# test-board-molex-bias-tee.net
KiCad netlist of a schematic drawn in Altium Designer
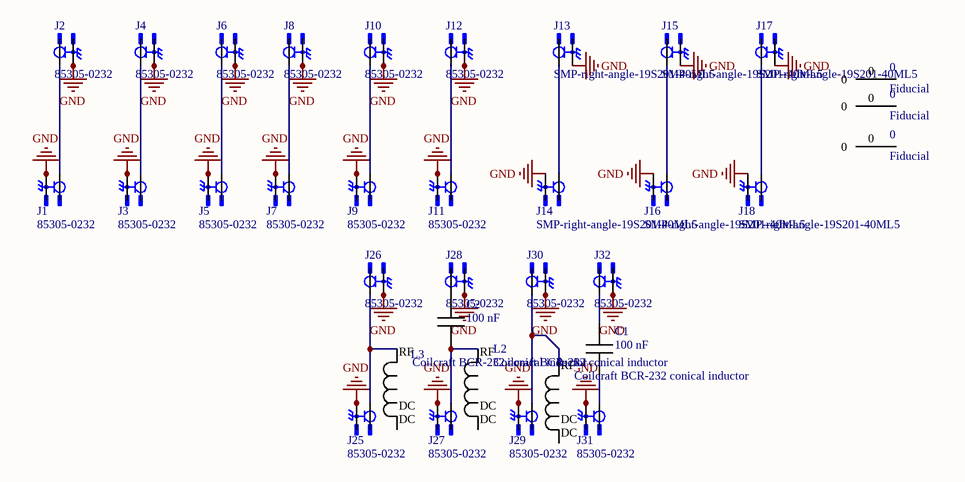
[diagram p0: test-board-molex-bias-tee.SchDoc]

(export (version "E")
  (design (tool "Eeschema 10.0.6"))
  (components
    (comp (ref "0") (value "Fiducial") (footprint "fiducial") (libsource (lib "Fiducial") (part "Fiducial")))
    (comp (ref "C1")
      (value "100 nF")
      (footprint "0201-capacitor")
      (description "BROADBAND CAPACITOR, 100 nF, 0201")
      (libsource (lib "SchlibLafe") (part "100 nF DC block capacitor 0201"))
    )
    (comp (ref "C2")
      (value "100 nF")
      (footprint "0201-capacitor")
      (description "BROADBAND CAPACITOR, 100 nF, 0201")
      (libsource (lib "SchlibLafe") (part "100 nF DC block capacitor 0201"))
    )
    (comp (ref "J1")
      (value "85305-0232")
      (footprint "MOLEX_85305-0232")
      (description "SMP Connector Plug, Male Pin 50Ohm Surface Mount Solder")
      (fields (field (name "MP") "853050232") (field (name "MF") "Molex"))
      (libsource (lib "") (part "85305-0232_1"))
    )
    (comp (ref "J2")
      (value "85305-0232")
      (footprint "MOLEX_85305-0232")
      (description "SMP Connector Plug, Male Pin 50Ohm Surface Mount Solder")
      (fields (field (name "MP") "853050232") (field (name "MF") "Molex"))
      (libsource (lib "85305-0232") (part "85305-0232"))
    )
    (comp (ref "J3")
      (value "85305-0232")
      (footprint "MOLEX_85305-0232")
      (description "SMP Connector Plug, Male Pin 50Ohm Surface Mount Solder")
      (fields (field (name "MP") "853050232") (field (name "MF") "Molex"))
      (libsource (lib "") (part "85305-0232_1"))
    )
    (comp (ref "J4")
      (value "85305-0232")
      (footprint "MOLEX_85305-0232")
      (description "SMP Connector Plug, Male Pin 50Ohm Surface Mount Solder")
      (fields (field (name "MP") "853050232") (field (name "MF") "Molex"))
      (libsource (lib "85305-0232") (part "85305-0232"))
    )
    (comp (ref "J5")
      (value "85305-0232")
      (footprint "MOLEX_85305-0232")
      (description "SMP Connector Plug, Male Pin 50Ohm Surface Mount Solder")
      (fields (field (name "MP") "853050232") (field (name "MF") "Molex"))
      (libsource (lib "") (part "85305-0232_1"))
    )
    (comp (ref "J6")
      (value "85305-0232")
      (footprint "MOLEX_85305-0232")
      (description "SMP Connector Plug, Male Pin 50Ohm Surface Mount Solder")
      (fields (field (name "MP") "853050232") (field (name "MF") "Molex"))
      (libsource (lib "85305-0232") (part "85305-0232"))
    )
    (comp (ref "J7")
      (value "85305-0232")
      (footprint "MOLEX_85305-0232")
      (description "SMP Connector Plug, Male Pin 50Ohm Surface Mount Solder")
      (fields (field (name "MP") "853050232") (field (name "MF") "Molex"))
      (libsource (lib "") (part "85305-0232_1"))
    )
    (comp (ref "J8")
      (value "85305-0232")
      (footprint "MOLEX_85305-0232")
      (description "SMP Connector Plug, Male Pin 50Ohm Surface Mount Solder")
      (fields (field (name "MP") "853050232") (field (name "MF") "Molex"))
      (libsource (lib "85305-0232") (part "85305-0232"))
    )
    (comp (ref "J9")
      (value "85305-0232")
      (footprint "MOLEX_85305-0232")
      (description "SMP Connector Plug, Male Pin 50Ohm Surface Mount Solder")
      (fields (field (name "MP") "853050232") (field (name "MF") "Molex"))
      (libsource (lib "") (part "85305-0232_1"))
    )
    (comp (ref "J10")
      (value "85305-0232")
      (footprint "MOLEX_85305-0232")
      (description "SMP Connector Plug, Male Pin 50Ohm Surface Mount Solder")
      (fields (field (name "MP") "853050232") (field (name "MF") "Molex"))
      (libsource (lib "85305-0232") (part "85305-0232"))
    )
    (comp (ref "J11")
      (value "85305-0232")
      (footprint "MOLEX_85305-0232")
      (description "SMP Connector Plug, Male Pin 50Ohm Surface Mount Solder")
      (fields (field (name "MP") "853050232") (field (name "MF") "Molex"))
      (libsource (lib "") (part "85305-0232_1"))
    )
    (comp (ref "J12")
      (value "85305-0232")
      (footprint "MOLEX_85305-0232")
      (description "SMP Connector Plug, Male Pin 50Ohm Surface Mount Solder")
      (fields (field (name "MP") "853050232") (field (name "MF") "Molex"))
      (libsource (lib "85305-0232") (part "85305-0232"))
    )
    (comp (ref "J13")
      (value "SMP-right-angle-19S201-40ML5")
      (footprint "rosenberger-19S201-40ML5")
      (description "SMOOTH BORE SMP Connector Plug, Male Pin 50Ohm Surface Mount Solder")
      (fields (field (name "MP") "853050232") (field (name "MF") "Molex"))
      (libsource (lib "") (part "SMP-right-angle-19S201-40ML5_1"))
    )
    (comp (ref "J14")
      (value "SMP-right-angle-19S201-40ML5")
      (footprint "rosenberger-19S201-40ML5")
      (description "SMOOTH BORE SMP Connector Plug, Male Pin 50Ohm Surface Mount Solder")
      (fields (field (name "MP") "853050232") (field (name "MF") "Molex"))
      (libsource (lib "SchlibLafe") (part "SMP-right-angle-19S201-40ML5"))
    )
    (comp (ref "J15")
      (value "SMP-right-angle-19S201-40ML5")
      (footprint "rosenberger-19S201-40ML5")
      (description "SMOOTH BORE SMP Connector Plug, Male Pin 50Ohm Surface Mount Solder")
      (fields (field (name "MP") "853050232") (field (name "MF") "Molex"))
      (libsource (lib "") (part "SMP-right-angle-19S201-40ML5_1"))
    )
    (comp (ref "J16")
      (value "SMP-right-angle-19S201-40ML5")
      (footprint "rosenberger-19S201-40ML5")
      (description "SMOOTH BORE SMP Connector Plug, Male Pin 50Ohm Surface Mount Solder")
      (fields (field (name "MP") "853050232") (field (name "MF") "Molex"))
      (libsource (lib "SchlibLafe") (part "SMP-right-angle-19S201-40ML5"))
    )
    (comp (ref "J17")
      (value "SMP-right-angle-19S201-40ML5")
      (footprint "rosenberger-19S201-40ML5")
      (description "SMOOTH BORE SMP Connector Plug, Male Pin 50Ohm Surface Mount Solder")
      (fields (field (name "MP") "853050232") (field (name "MF") "Molex"))
      (libsource (lib "") (part "SMP-right-angle-19S201-40ML5_1"))
    )
    (comp (ref "J18")
      (value "SMP-right-angle-19S201-40ML5")
      (footprint "rosenberger-19S201-40ML5")
      (description "SMOOTH BORE SMP Connector Plug, Male Pin 50Ohm Surface Mount Solder")
      (fields (field (name "MP") "853050232") (field (name "MF") "Molex"))
      (libsource (lib "SchlibLafe") (part "SMP-right-angle-19S201-40ML5"))
    )
    (comp (ref "J25")
      (value "85305-0232")
      (footprint "MOLEX_85305-0232")
      (description "SMP Connector Plug, Male Pin 50Ohm Surface Mount Solder")
      (fields (field (name "MP") "853050232") (field (name "MF") "Molex"))
      (libsource (lib "") (part "85305-0232_1"))
    )
    (comp (ref "J26")
      (value "85305-0232")
      (footprint "MOLEX_85305-0232")
      (description "SMP Connector Plug, Male Pin 50Ohm Surface Mount Solder")
      (fields (field (name "MP") "853050232") (field (name "MF") "Molex"))
      (libsource (lib "85305-0232") (part "85305-0232"))
    )
    (comp (ref "J27")
      (value "85305-0232")
      (footprint "MOLEX_85305-0232")
      (description "SMP Connector Plug, Male Pin 50Ohm Surface Mount Solder")
      (fields (field (name "MP") "853050232") (field (name "MF") "Molex"))
      (libsource (lib "") (part "85305-0232_1"))
    )
    (comp (ref "J28")
      (value "85305-0232")
      (footprint "MOLEX_85305-0232")
      (description "SMP Connector Plug, Male Pin 50Ohm Surface Mount Solder")
      (fields (field (name "MP") "853050232") (field (name "MF") "Molex"))
      (libsource (lib "85305-0232") (part "85305-0232"))
    )
    (comp (ref "J29")
      (value "85305-0232")
      (footprint "MOLEX_85305-0232")
      (description "SMP Connector Plug, Male Pin 50Ohm Surface Mount Solder")
      (fields (field (name "MP") "853050232") (field (name "MF") "Molex"))
      (libsource (lib "") (part "85305-0232_1"))
    )
    (comp (ref "J30")
      (value "85305-0232")
      (footprint "MOLEX_85305-0232")
      (description "SMP Connector Plug, Male Pin 50Ohm Surface Mount Solder")
      (fields (field (name "MP") "853050232") (field (name "MF") "Molex"))
      (libsource (lib "85305-0232") (part "85305-0232"))
    )
    (comp (ref "J31")
      (value "85305-0232")
      (footprint "MOLEX_85305-0232")
      (description "SMP Connector Plug, Male Pin 50Ohm Surface Mount Solder")
      (fields (field (name "MP") "853050232") (field (name "MF") "Molex"))
      (libsource (lib "") (part "85305-0232_1"))
    )
    (comp (ref "J32")
      (value "85305-0232")
      (footprint "MOLEX_85305-0232")
      (description "SMP Connector Plug, Male Pin 50Ohm Surface Mount Solder")
      (fields (field (name "MP") "853050232") (field (name "MF") "Molex"))
      (libsource (lib "85305-0232") (part "85305-0232"))
    )
    (comp (ref "L1")
      (value "Coilcraft BCR-232 conical inductor")
      (footprint "Coilcraft BCR-232 conical inductor")
      (description "No Description Available")
      (libsource (lib "SchlibLafe") (part "Coilcraft BCR-232 conical inductor"))
    )
    (comp (ref "L2")
      (value "Coilcraft BCR-232 conical inductor")
      (footprint "Coilcraft BCR-232 conical inductor")
      (description "No Description Available")
      (libsource (lib "SchlibLafe") (part "Coilcraft BCR-232 conical inductor"))
    )
    (comp (ref "L3")
      (value "Coilcraft BCR-232 conical inductor")
      (footprint "Coilcraft BCR-232 conical inductor")
      (description "No Description Available")
      (libsource (lib "SchlibLafe") (part "Coilcraft BCR-232 conical inductor"))
    )
  )
  (nets
    (net (code "1") (name "GND") (class "Default")
      (node (ref "J1") (pin "10") (pinfunction "2_10") (pintype "passive"))
      (node (ref "J1") (pin "11") (pinfunction "2_11") (pintype "passive"))
      (node (ref "J1") (pin "12") (pinfunction "2_12") (pintype "passive"))
      (node (ref "J1") (pin "13") (pinfunction "2_13") (pintype "passive"))
      (node (ref "J1") (pin "14") (pinfunction "2_14") (pintype "passive"))
      (node (ref "J1") (pin "15") (pinfunction "2_15") (pintype "passive"))
      (node (ref "J1") (pin "16") (pinfunction "2_16") (pintype "passive"))
      (node (ref "J1") (pin "17") (pinfunction "2_17") (pintype "passive"))
      (node (ref "J1") (pin "18") (pinfunction "2_18") (pintype "passive"))
      (node (ref "J1") (pin "2") (pinfunction "2_2") (pintype "passive"))
      (node (ref "J1") (pin "3") (pinfunction "2_3") (pintype "passive"))
      (node (ref "J1") (pin "4") (pinfunction "2_4") (pintype "passive"))
      (node (ref "J1") (pin "5") (pinfunction "2_5") (pintype "passive"))
      (node (ref "J1") (pin "6") (pinfunction "2_6") (pintype "passive"))
      (node (ref "J1") (pin "7") (pinfunction "2_7") (pintype "passive"))
      (node (ref "J1") (pin "8") (pinfunction "2_8") (pintype "passive"))
      (node (ref "J1") (pin "9") (pinfunction "2_9") (pintype "passive"))
      (node (ref "J10") (pin "10") (pinfunction "2_10") (pintype "passive"))
      (node (ref "J10") (pin "11") (pinfunction "2_11") (pintype "passive"))
      (node (ref "J10") (pin "12") (pinfunction "2_12") (pintype "passive"))
      (node (ref "J10") (pin "13") (pinfunction "2_13") (pintype "passive"))
      (node (ref "J10") (pin "14") (pinfunction "2_14") (pintype "passive"))
      (node (ref "J10") (pin "15") (pinfunction "2_15") (pintype "passive"))
      (node (ref "J10") (pin "16") (pinfunction "2_16") (pintype "passive"))
      (node (ref "J10") (pin "17") (pinfunction "2_17") (pintype "passive"))
      (node (ref "J10") (pin "18") (pinfunction "2_18") (pintype "passive"))
      (node (ref "J10") (pin "2") (pinfunction "2_2") (pintype "passive"))
      (node (ref "J10") (pin "3") (pinfunction "2_3") (pintype "passive"))
      (node (ref "J10") (pin "4") (pinfunction "2_4") (pintype "passive"))
      (node (ref "J10") (pin "5") (pinfunction "2_5") (pintype "passive"))
      (node (ref "J10") (pin "6") (pinfunction "2_6") (pintype "passive"))
      (node (ref "J10") (pin "7") (pinfunction "2_7") (pintype "passive"))
      (node (ref "J10") (pin "8") (pinfunction "2_8") (pintype "passive"))
      (node (ref "J10") (pin "9") (pinfunction "2_9") (pintype "passive"))
      (node (ref "J11") (pin "10") (pinfunction "2_10") (pintype "passive"))
      (node (ref "J11") (pin "11") (pinfunction "2_11") (pintype "passive"))
      (node (ref "J11") (pin "12") (pinfunction "2_12") (pintype "passive"))
      (node (ref "J11") (pin "13") (pinfunction "2_13") (pintype "passive"))
      (node (ref "J11") (pin "14") (pinfunction "2_14") (pintype "passive"))
      (node (ref "J11") (pin "15") (pinfunction "2_15") (pintype "passive"))
      (node (ref "J11") (pin "16") (pinfunction "2_16") (pintype "passive"))
      (node (ref "J11") (pin "17") (pinfunction "2_17") (pintype "passive"))
      (node (ref "J11") (pin "18") (pinfunction "2_18") (pintype "passive"))
      (node (ref "J11") (pin "2") (pinfunction "2_2") (pintype "passive"))
      (node (ref "J11") (pin "3") (pinfunction "2_3") (pintype "passive"))
      (node (ref "J11") (pin "4") (pinfunction "2_4") (pintype "passive"))
      (node (ref "J11") (pin "5") (pinfunction "2_5") (pintype "passive"))
      (node (ref "J11") (pin "6") (pinfunction "2_6") (pintype "passive"))
      (node (ref "J11") (pin "7") (pinfunction "2_7") (pintype "passive"))
      (node (ref "J11") (pin "8") (pinfunction "2_8") (pintype "passive"))
      (node (ref "J11") (pin "9") (pinfunction "2_9") (pintype "passive"))
      (node (ref "J12") (pin "10") (pinfunction "2_10") (pintype "passive"))
      (node (ref "J12") (pin "11") (pinfunction "2_11") (pintype "passive"))
      (node (ref "J12") (pin "12") (pinfunction "2_12") (pintype "passive"))
      (node (ref "J12") (pin "13") (pinfunction "2_13") (pintype "passive"))
      (node (ref "J12") (pin "14") (pinfunction "2_14") (pintype "passive"))
      (node (ref "J12") (pin "15") (pinfunction "2_15") (pintype "passive"))
      (node (ref "J12") (pin "16") (pinfunction "2_16") (pintype "passive"))
      (node (ref "J12") (pin "17") (pinfunction "2_17") (pintype "passive"))
      (node (ref "J12") (pin "18") (pinfunction "2_18") (pintype "passive"))
      (node (ref "J12") (pin "2") (pinfunction "2_2") (pintype "passive"))
      (node (ref "J12") (pin "3") (pinfunction "2_3") (pintype "passive"))
      (node (ref "J12") (pin "4") (pinfunction "2_4") (pintype "passive"))
      (node (ref "J12") (pin "5") (pinfunction "2_5") (pintype "passive"))
      (node (ref "J12") (pin "6") (pinfunction "2_6") (pintype "passive"))
      (node (ref "J12") (pin "7") (pinfunction "2_7") (pintype "passive"))
      (node (ref "J12") (pin "8") (pinfunction "2_8") (pintype "passive"))
      (node (ref "J12") (pin "9") (pinfunction "2_9") (pintype "passive"))
      (node (ref "J13") (pin "gnd") (pinfunction "gnd_gnd") (pintype "passive"))
      (node (ref "J14") (pin "gnd") (pinfunction "gnd_gnd") (pintype "passive"))
      (node (ref "J15") (pin "gnd") (pinfunction "gnd_gnd") (pintype "passive"))
      (node (ref "J16") (pin "gnd") (pinfunction "gnd_gnd") (pintype "passive"))
      (node (ref "J17") (pin "gnd") (pinfunction "gnd_gnd") (pintype "passive"))
      (node (ref "J18") (pin "gnd") (pinfunction "gnd_gnd") (pintype "passive"))
      (node (ref "J2") (pin "10") (pinfunction "2_10") (pintype "passive"))
      (node (ref "J2") (pin "11") (pinfunction "2_11") (pintype "passive"))
      (node (ref "J2") (pin "12") (pinfunction "2_12") (pintype "passive"))
      (node (ref "J2") (pin "13") (pinfunction "2_13") (pintype "passive"))
      (node (ref "J2") (pin "14") (pinfunction "2_14") (pintype "passive"))
      (node (ref "J2") (pin "15") (pinfunction "2_15") (pintype "passive"))
      (node (ref "J2") (pin "16") (pinfunction "2_16") (pintype "passive"))
      (node (ref "J2") (pin "17") (pinfunction "2_17") (pintype "passive"))
      (node (ref "J2") (pin "18") (pinfunction "2_18") (pintype "passive"))
      (node (ref "J2") (pin "2") (pinfunction "2_2") (pintype "passive"))
      (node (ref "J2") (pin "3") (pinfunction "2_3") (pintype "passive"))
      (node (ref "J2") (pin "4") (pinfunction "2_4") (pintype "passive"))
      (node (ref "J2") (pin "5") (pinfunction "2_5") (pintype "passive"))
      (node (ref "J2") (pin "6") (pinfunction "2_6") (pintype "passive"))
      (node (ref "J2") (pin "7") (pinfunction "2_7") (pintype "passive"))
      (node (ref "J2") (pin "8") (pinfunction "2_8") (pintype "passive"))
      (node (ref "J2") (pin "9") (pinfunction "2_9") (pintype "passive"))
      (node (ref "J25") (pin "10") (pinfunction "2_10") (pintype "passive"))
      (node (ref "J25") (pin "11") (pinfunction "2_11") (pintype "passive"))
      (node (ref "J25") (pin "12") (pinfunction "2_12") (pintype "passive"))
      (node (ref "J25") (pin "13") (pinfunction "2_13") (pintype "passive"))
      (node (ref "J25") (pin "14") (pinfunction "2_14") (pintype "passive"))
      (node (ref "J25") (pin "15") (pinfunction "2_15") (pintype "passive"))
      (node (ref "J25") (pin "16") (pinfunction "2_16") (pintype "passive"))
      (node (ref "J25") (pin "17") (pinfunction "2_17") (pintype "passive"))
      (node (ref "J25") (pin "18") (pinfunction "2_18") (pintype "passive"))
      (node (ref "J25") (pin "2") (pinfunction "2_2") (pintype "passive"))
      (node (ref "J25") (pin "3") (pinfunction "2_3") (pintype "passive"))
      (node (ref "J25") (pin "4") (pinfunction "2_4") (pintype "passive"))
      (node (ref "J25") (pin "5") (pinfunction "2_5") (pintype "passive"))
      (node (ref "J25") (pin "6") (pinfunction "2_6") (pintype "passive"))
      (node (ref "J25") (pin "7") (pinfunction "2_7") (pintype "passive"))
      (node (ref "J25") (pin "8") (pinfunction "2_8") (pintype "passive"))
      (node (ref "J25") (pin "9") (pinfunction "2_9") (pintype "passive"))
      (node (ref "J26") (pin "10") (pinfunction "2_10") (pintype "passive"))
      (node (ref "J26") (pin "11") (pinfunction "2_11") (pintype "passive"))
      (node (ref "J26") (pin "12") (pinfunction "2_12") (pintype "passive"))
      (node (ref "J26") (pin "13") (pinfunction "2_13") (pintype "passive"))
      (node (ref "J26") (pin "14") (pinfunction "2_14") (pintype "passive"))
      (node (ref "J26") (pin "15") (pinfunction "2_15") (pintype "passive"))
      (node (ref "J26") (pin "16") (pinfunction "2_16") (pintype "passive"))
      (node (ref "J26") (pin "17") (pinfunction "2_17") (pintype "passive"))
      (node (ref "J26") (pin "18") (pinfunction "2_18") (pintype "passive"))
      (node (ref "J26") (pin "2") (pinfunction "2_2") (pintype "passive"))
      (node (ref "J26") (pin "3") (pinfunction "2_3") (pintype "passive"))
      (node (ref "J26") (pin "4") (pinfunction "2_4") (pintype "passive"))
      (node (ref "J26") (pin "5") (pinfunction "2_5") (pintype "passive"))
      (node (ref "J26") (pin "6") (pinfunction "2_6") (pintype "passive"))
      (node (ref "J26") (pin "7") (pinfunction "2_7") (pintype "passive"))
      (node (ref "J26") (pin "8") (pinfunction "2_8") (pintype "passive"))
      (node (ref "J26") (pin "9") (pinfunction "2_9") (pintype "passive"))
      (node (ref "J27") (pin "10") (pinfunction "2_10") (pintype "passive"))
      (node (ref "J27") (pin "11") (pinfunction "2_11") (pintype "passive"))
      (node (ref "J27") (pin "12") (pinfunction "2_12") (pintype "passive"))
      (node (ref "J27") (pin "13") (pinfunction "2_13") (pintype "passive"))
      (node (ref "J27") (pin "14") (pinfunction "2_14") (pintype "passive"))
      (node (ref "J27") (pin "15") (pinfunction "2_15") (pintype "passive"))
      (node (ref "J27") (pin "16") (pinfunction "2_16") (pintype "passive"))
      (node (ref "J27") (pin "17") (pinfunction "2_17") (pintype "passive"))
      (node (ref "J27") (pin "18") (pinfunction "2_18") (pintype "passive"))
      (node (ref "J27") (pin "2") (pinfunction "2_2") (pintype "passive"))
      (node (ref "J27") (pin "3") (pinfunction "2_3") (pintype "passive"))
      (node (ref "J27") (pin "4") (pinfunction "2_4") (pintype "passive"))
      (node (ref "J27") (pin "5") (pinfunction "2_5") (pintype "passive"))
      (node (ref "J27") (pin "6") (pinfunction "2_6") (pintype "passive"))
      (node (ref "J27") (pin "7") (pinfunction "2_7") (pintype "passive"))
      (node (ref "J27") (pin "8") (pinfunction "2_8") (pintype "passive"))
      (node (ref "J27") (pin "9") (pinfunction "2_9") (pintype "passive"))
      (node (ref "J28") (pin "10") (pinfunction "2_10") (pintype "passive"))
      (node (ref "J28") (pin "11") (pinfunction "2_11") (pintype "passive"))
      (node (ref "J28") (pin "12") (pinfunction "2_12") (pintype "passive"))
      (node (ref "J28") (pin "13") (pinfunction "2_13") (pintype "passive"))
      (node (ref "J28") (pin "14") (pinfunction "2_14") (pintype "passive"))
      (node (ref "J28") (pin "15") (pinfunction "2_15") (pintype "passive"))
      (node (ref "J28") (pin "16") (pinfunction "2_16") (pintype "passive"))
      (node (ref "J28") (pin "17") (pinfunction "2_17") (pintype "passive"))
      (node (ref "J28") (pin "18") (pinfunction "2_18") (pintype "passive"))
      (node (ref "J28") (pin "2") (pinfunction "2_2") (pintype "passive"))
      (node (ref "J28") (pin "3") (pinfunction "2_3") (pintype "passive"))
      (node (ref "J28") (pin "4") (pinfunction "2_4") (pintype "passive"))
      (node (ref "J28") (pin "5") (pinfunction "2_5") (pintype "passive"))
      (node (ref "J28") (pin "6") (pinfunction "2_6") (pintype "passive"))
      (node (ref "J28") (pin "7") (pinfunction "2_7") (pintype "passive"))
      (node (ref "J28") (pin "8") (pinfunction "2_8") (pintype "passive"))
      (node (ref "J28") (pin "9") (pinfunction "2_9") (pintype "passive"))
      (node (ref "J29") (pin "10") (pinfunction "2_10") (pintype "passive"))
      (node (ref "J29") (pin "11") (pinfunction "2_11") (pintype "passive"))
      (node (ref "J29") (pin "12") (pinfunction "2_12") (pintype "passive"))
      (node (ref "J29") (pin "13") (pinfunction "2_13") (pintype "passive"))
      (node (ref "J29") (pin "14") (pinfunction "2_14") (pintype "passive"))
      (node (ref "J29") (pin "15") (pinfunction "2_15") (pintype "passive"))
      (node (ref "J29") (pin "16") (pinfunction "2_16") (pintype "passive"))
      (node (ref "J29") (pin "17") (pinfunction "2_17") (pintype "passive"))
      (node (ref "J29") (pin "18") (pinfunction "2_18") (pintype "passive"))
      (node (ref "J29") (pin "2") (pinfunction "2_2") (pintype "passive"))
      (node (ref "J29") (pin "3") (pinfunction "2_3") (pintype "passive"))
      (node (ref "J29") (pin "4") (pinfunction "2_4") (pintype "passive"))
      (node (ref "J29") (pin "5") (pinfunction "2_5") (pintype "passive"))
      (node (ref "J29") (pin "6") (pinfunction "2_6") (pintype "passive"))
      (node (ref "J29") (pin "7") (pinfunction "2_7") (pintype "passive"))
      (node (ref "J29") (pin "8") (pinfunction "2_8") (pintype "passive"))
      (node (ref "J29") (pin "9") (pinfunction "2_9") (pintype "passive"))
      (node (ref "J3") (pin "10") (pinfunction "2_10") (pintype "passive"))
      (node (ref "J3") (pin "11") (pinfunction "2_11") (pintype "passive"))
      (node (ref "J3") (pin "12") (pinfunction "2_12") (pintype "passive"))
      (node (ref "J3") (pin "13") (pinfunction "2_13") (pintype "passive"))
      (node (ref "J3") (pin "14") (pinfunction "2_14") (pintype "passive"))
      (node (ref "J3") (pin "15") (pinfunction "2_15") (pintype "passive"))
      (node (ref "J3") (pin "16") (pinfunction "2_16") (pintype "passive"))
      (node (ref "J3") (pin "17") (pinfunction "2_17") (pintype "passive"))
      (node (ref "J3") (pin "18") (pinfunction "2_18") (pintype "passive"))
      (node (ref "J3") (pin "2") (pinfunction "2_2") (pintype "passive"))
      (node (ref "J3") (pin "3") (pinfunction "2_3") (pintype "passive"))
      (node (ref "J3") (pin "4") (pinfunction "2_4") (pintype "passive"))
      (node (ref "J3") (pin "5") (pinfunction "2_5") (pintype "passive"))
      (node (ref "J3") (pin "6") (pinfunction "2_6") (pintype "passive"))
      (node (ref "J3") (pin "7") (pinfunction "2_7") (pintype "passive"))
      (node (ref "J3") (pin "8") (pinfunction "2_8") (pintype "passive"))
      (node (ref "J3") (pin "9") (pinfunction "2_9") (pintype "passive"))
      (node (ref "J30") (pin "10") (pinfunction "2_10") (pintype "passive"))
      (node (ref "J30") (pin "11") (pinfunction "2_11") (pintype "passive"))
      (node (ref "J30") (pin "12") (pinfunction "2_12") (pintype "passive"))
      (node (ref "J30") (pin "13") (pinfunction "2_13") (pintype "passive"))
      (node (ref "J30") (pin "14") (pinfunction "2_14") (pintype "passive"))
      (node (ref "J30") (pin "15") (pinfunction "2_15") (pintype "passive"))
      (node (ref "J30") (pin "16") (pinfunction "2_16") (pintype "passive"))
      (node (ref "J30") (pin "17") (pinfunction "2_17") (pintype "passive"))
      (node (ref "J30") (pin "18") (pinfunction "2_18") (pintype "passive"))
      (node (ref "J30") (pin "2") (pinfunction "2_2") (pintype "passive"))
      (node (ref "J30") (pin "3") (pinfunction "2_3") (pintype "passive"))
      (node (ref "J30") (pin "4") (pinfunction "2_4") (pintype "passive"))
      (node (ref "J30") (pin "5") (pinfunction "2_5") (pintype "passive"))
      (node (ref "J30") (pin "6") (pinfunction "2_6") (pintype "passive"))
      (node (ref "J30") (pin "7") (pinfunction "2_7") (pintype "passive"))
      (node (ref "J30") (pin "8") (pinfunction "2_8") (pintype "passive"))
      (node (ref "J30") (pin "9") (pinfunction "2_9") (pintype "passive"))
      (node (ref "J31") (pin "10") (pinfunction "2_10") (pintype "passive"))
      (node (ref "J31") (pin "11") (pinfunction "2_11") (pintype "passive"))
      (node (ref "J31") (pin "12") (pinfunction "2_12") (pintype "passive"))
      (node (ref "J31") (pin "13") (pinfunction "2_13") (pintype "passive"))
      (node (ref "J31") (pin "14") (pinfunction "2_14") (pintype "passive"))
      (node (ref "J31") (pin "15") (pinfunction "2_15") (pintype "passive"))
      (node (ref "J31") (pin "16") (pinfunction "2_16") (pintype "passive"))
      (node (ref "J31") (pin "17") (pinfunction "2_17") (pintype "passive"))
      (node (ref "J31") (pin "18") (pinfunction "2_18") (pintype "passive"))
      (node (ref "J31") (pin "2") (pinfunction "2_2") (pintype "passive"))
      (node (ref "J31") (pin "3") (pinfunction "2_3") (pintype "passive"))
      (node (ref "J31") (pin "4") (pinfunction "2_4") (pintype "passive"))
      (node (ref "J31") (pin "5") (pinfunction "2_5") (pintype "passive"))
      (node (ref "J31") (pin "6") (pinfunction "2_6") (pintype "passive"))
      (node (ref "J31") (pin "7") (pinfunction "2_7") (pintype "passive"))
      (node (ref "J31") (pin "8") (pinfunction "2_8") (pintype "passive"))
      (node (ref "J31") (pin "9") (pinfunction "2_9") (pintype "passive"))
      (node (ref "J32") (pin "10") (pinfunction "2_10") (pintype "passive"))
      (node (ref "J32") (pin "11") (pinfunction "2_11") (pintype "passive"))
      (node (ref "J32") (pin "12") (pinfunction "2_12") (pintype "passive"))
      (node (ref "J32") (pin "13") (pinfunction "2_13") (pintype "passive"))
      (node (ref "J32") (pin "14") (pinfunction "2_14") (pintype "passive"))
      (node (ref "J32") (pin "15") (pinfunction "2_15") (pintype "passive"))
      (node (ref "J32") (pin "16") (pinfunction "2_16") (pintype "passive"))
      (node (ref "J32") (pin "17") (pinfunction "2_17") (pintype "passive"))
      (node (ref "J32") (pin "18") (pinfunction "2_18") (pintype "passive"))
      (node (ref "J32") (pin "2") (pinfunction "2_2") (pintype "passive"))
      (node (ref "J32") (pin "3") (pinfunction "2_3") (pintype "passive"))
      (node (ref "J32") (pin "4") (pinfunction "2_4") (pintype "passive"))
      (node (ref "J32") (pin "5") (pinfunction "2_5") (pintype "passive"))
      (node (ref "J32") (pin "6") (pinfunction "2_6") (pintype "passive"))
      (node (ref "J32") (pin "7") (pinfunction "2_7") (pintype "passive"))
      (node (ref "J32") (pin "8") (pinfunction "2_8") (pintype "passive"))
      (node (ref "J32") (pin "9") (pinfunction "2_9") (pintype "passive"))
      (node (ref "J4") (pin "10") (pinfunction "2_10") (pintype "passive"))
      (node (ref "J4") (pin "11") (pinfunction "2_11") (pintype "passive"))
      (node (ref "J4") (pin "12") (pinfunction "2_12") (pintype "passive"))
      (node (ref "J4") (pin "13") (pinfunction "2_13") (pintype "passive"))
      (node (ref "J4") (pin "14") (pinfunction "2_14") (pintype "passive"))
      (node (ref "J4") (pin "15") (pinfunction "2_15") (pintype "passive"))
      (node (ref "J4") (pin "16") (pinfunction "2_16") (pintype "passive"))
      (node (ref "J4") (pin "17") (pinfunction "2_17") (pintype "passive"))
      (node (ref "J4") (pin "18") (pinfunction "2_18") (pintype "passive"))
      (node (ref "J4") (pin "2") (pinfunction "2_2") (pintype "passive"))
      (node (ref "J4") (pin "3") (pinfunction "2_3") (pintype "passive"))
      (node (ref "J4") (pin "4") (pinfunction "2_4") (pintype "passive"))
      (node (ref "J4") (pin "5") (pinfunction "2_5") (pintype "passive"))
      (node (ref "J4") (pin "6") (pinfunction "2_6") (pintype "passive"))
      (node (ref "J4") (pin "7") (pinfunction "2_7") (pintype "passive"))
      (node (ref "J4") (pin "8") (pinfunction "2_8") (pintype "passive"))
      (node (ref "J4") (pin "9") (pinfunction "2_9") (pintype "passive"))
      (node (ref "J5") (pin "10") (pinfunction "2_10") (pintype "passive"))
      (node (ref "J5") (pin "11") (pinfunction "2_11") (pintype "passive"))
      (node (ref "J5") (pin "12") (pinfunction "2_12") (pintype "passive"))
      (node (ref "J5") (pin "13") (pinfunction "2_13") (pintype "passive"))
      (node (ref "J5") (pin "14") (pinfunction "2_14") (pintype "passive"))
      (node (ref "J5") (pin "15") (pinfunction "2_15") (pintype "passive"))
      (node (ref "J5") (pin "16") (pinfunction "2_16") (pintype "passive"))
      (node (ref "J5") (pin "17") (pinfunction "2_17") (pintype "passive"))
      (node (ref "J5") (pin "18") (pinfunction "2_18") (pintype "passive"))
      (node (ref "J5") (pin "2") (pinfunction "2_2") (pintype "passive"))
      (node (ref "J5") (pin "3") (pinfunction "2_3") (pintype "passive"))
      (node (ref "J5") (pin "4") (pinfunction "2_4") (pintype "passive"))
      (node (ref "J5") (pin "5") (pinfunction "2_5") (pintype "passive"))
      (node (ref "J5") (pin "6") (pinfunction "2_6") (pintype "passive"))
      (node (ref "J5") (pin "7") (pinfunction "2_7") (pintype "passive"))
      (node (ref "J5") (pin "8") (pinfunction "2_8") (pintype "passive"))
      (node (ref "J5") (pin "9") (pinfunction "2_9") (pintype "passive"))
      (node (ref "J6") (pin "10") (pinfunction "2_10") (pintype "passive"))
      (node (ref "J6") (pin "11") (pinfunction "2_11") (pintype "passive"))
      (node (ref "J6") (pin "12") (pinfunction "2_12") (pintype "passive"))
      (node (ref "J6") (pin "13") (pinfunction "2_13") (pintype "passive"))
      (node (ref "J6") (pin "14") (pinfunction "2_14") (pintype "passive"))
      (node (ref "J6") (pin "15") (pinfunction "2_15") (pintype "passive"))
      (node (ref "J6") (pin "16") (pinfunction "2_16") (pintype "passive"))
      (node (ref "J6") (pin "17") (pinfunction "2_17") (pintype "passive"))
      (node (ref "J6") (pin "18") (pinfunction "2_18") (pintype "passive"))
      (node (ref "J6") (pin "2") (pinfunction "2_2") (pintype "passive"))
      (node (ref "J6") (pin "3") (pinfunction "2_3") (pintype "passive"))
      (node (ref "J6") (pin "4") (pinfunction "2_4") (pintype "passive"))
      (node (ref "J6") (pin "5") (pinfunction "2_5") (pintype "passive"))
      (node (ref "J6") (pin "6") (pinfunction "2_6") (pintype "passive"))
      (node (ref "J6") (pin "7") (pinfunction "2_7") (pintype "passive"))
      (node (ref "J6") (pin "8") (pinfunction "2_8") (pintype "passive"))
      (node (ref "J6") (pin "9") (pinfunction "2_9") (pintype "passive"))
      (node (ref "J7") (pin "10") (pinfunction "2_10") (pintype "passive"))
      (node (ref "J7") (pin "11") (pinfunction "2_11") (pintype "passive"))
      (node (ref "J7") (pin "12") (pinfunction "2_12") (pintype "passive"))
      (node (ref "J7") (pin "13") (pinfunction "2_13") (pintype "passive"))
      (node (ref "J7") (pin "14") (pinfunction "2_14") (pintype "passive"))
      (node (ref "J7") (pin "15") (pinfunction "2_15") (pintype "passive"))
      (node (ref "J7") (pin "16") (pinfunction "2_16") (pintype "passive"))
      (node (ref "J7") (pin "17") (pinfunction "2_17") (pintype "passive"))
      (node (ref "J7") (pin "18") (pinfunction "2_18") (pintype "passive"))
      (node (ref "J7") (pin "2") (pinfunction "2_2") (pintype "passive"))
      (node (ref "J7") (pin "3") (pinfunction "2_3") (pintype "passive"))
      (node (ref "J7") (pin "4") (pinfunction "2_4") (pintype "passive"))
      (node (ref "J7") (pin "5") (pinfunction "2_5") (pintype "passive"))
      (node (ref "J7") (pin "6") (pinfunction "2_6") (pintype "passive"))
      (node (ref "J7") (pin "7") (pinfunction "2_7") (pintype "passive"))
      (node (ref "J7") (pin "8") (pinfunction "2_8") (pintype "passive"))
      (node (ref "J7") (pin "9") (pinfunction "2_9") (pintype "passive"))
      (node (ref "J8") (pin "10") (pinfunction "2_10") (pintype "passive"))
      (node (ref "J8") (pin "11") (pinfunction "2_11") (pintype "passive"))
      (node (ref "J8") (pin "12") (pinfunction "2_12") (pintype "passive"))
      (node (ref "J8") (pin "13") (pinfunction "2_13") (pintype "passive"))
      (node (ref "J8") (pin "14") (pinfunction "2_14") (pintype "passive"))
      (node (ref "J8") (pin "15") (pinfunction "2_15") (pintype "passive"))
      (node (ref "J8") (pin "16") (pinfunction "2_16") (pintype "passive"))
      (node (ref "J8") (pin "17") (pinfunction "2_17") (pintype "passive"))
      (node (ref "J8") (pin "18") (pinfunction "2_18") (pintype "passive"))
      (node (ref "J8") (pin "2") (pinfunction "2_2") (pintype "passive"))
      (node (ref "J8") (pin "3") (pinfunction "2_3") (pintype "passive"))
      (node (ref "J8") (pin "4") (pinfunction "2_4") (pintype "passive"))
      (node (ref "J8") (pin "5") (pinfunction "2_5") (pintype "passive"))
      (node (ref "J8") (pin "6") (pinfunction "2_6") (pintype "passive"))
      (node (ref "J8") (pin "7") (pinfunction "2_7") (pintype "passive"))
      (node (ref "J8") (pin "8") (pinfunction "2_8") (pintype "passive"))
      (node (ref "J8") (pin "9") (pinfunction "2_9") (pintype "passive"))
      (node (ref "J9") (pin "10") (pinfunction "2_10") (pintype "passive"))
      (node (ref "J9") (pin "11") (pinfunction "2_11") (pintype "passive"))
      (node (ref "J9") (pin "12") (pinfunction "2_12") (pintype "passive"))
      (node (ref "J9") (pin "13") (pinfunction "2_13") (pintype "passive"))
      (node (ref "J9") (pin "14") (pinfunction "2_14") (pintype "passive"))
      (node (ref "J9") (pin "15") (pinfunction "2_15") (pintype "passive"))
      (node (ref "J9") (pin "16") (pinfunction "2_16") (pintype "passive"))
      (node (ref "J9") (pin "17") (pinfunction "2_17") (pintype "passive"))
      (node (ref "J9") (pin "18") (pinfunction "2_18") (pintype "passive"))
      (node (ref "J9") (pin "2") (pinfunction "2_2") (pintype "passive"))
      (node (ref "J9") (pin "3") (pinfunction "2_3") (pintype "passive"))
      (node (ref "J9") (pin "4") (pinfunction "2_4") (pintype "passive"))
      (node (ref "J9") (pin "5") (pinfunction "2_5") (pintype "passive"))
      (node (ref "J9") (pin "6") (pinfunction "2_6") (pintype "passive"))
      (node (ref "J9") (pin "7") (pinfunction "2_7") (pintype "passive"))
      (node (ref "J9") (pin "8") (pinfunction "2_8") (pintype "passive"))
      (node (ref "J9") (pin "9") (pinfunction "2_9") (pintype "passive"))
    )
    (net (code "2") (name "Net-(C1-Pad1)") (class "Default")
      (node (ref "C1") (pin "1") (pinfunction "1_1") (pintype "passive"))
      (node (ref "J31") (pin "1") (pinfunction "1_1") (pintype "passive"))
    )
    (net (code "3") (name "Net-(C1-Pad2)") (class "Default")
      (node (ref "C1") (pin "2") (pinfunction "2_2") (pintype "passive"))
      (node (ref "J32") (pin "1") (pinfunction "1_1") (pintype "passive"))
    )
    (net (code "4") (name "Net-(C2-Pad1)") (class "Default")
      (node (ref "C2") (pin "1") (pinfunction "1_1") (pintype "passive"))
      (node (ref "J27") (pin "1") (pinfunction "1_1") (pintype "passive"))
      (node (ref "L2") (pin "1") (pinfunction "1_1") (pintype "passive"))
    )
    (net (code "5") (name "Net-(C2-Pad2)") (class "Default")
      (node (ref "C2") (pin "2") (pinfunction "2_2") (pintype "passive"))
      (node (ref "J28") (pin "1") (pinfunction "1_1") (pintype "passive"))
    )
    (net (code "6") (name "Net-(J1-Pad1)") (class "Default")
      (node (ref "J1") (pin "1") (pinfunction "1_1") (pintype "passive"))
      (node (ref "J2") (pin "1") (pinfunction "1_1") (pintype "passive"))
    )
    (net (code "7") (name "Net-(J3-Pad1)") (class "Default")
      (node (ref "J3") (pin "1") (pinfunction "1_1") (pintype "passive"))
      (node (ref "J4") (pin "1") (pinfunction "1_1") (pintype "passive"))
    )
    (net (code "8") (name "Net-(J5-Pad1)") (class "Default")
      (node (ref "J5") (pin "1") (pinfunction "1_1") (pintype "passive"))
      (node (ref "J6") (pin "1") (pinfunction "1_1") (pintype "passive"))
    )
    (net (code "9") (name "Net-(J7-Pad1)") (class "Default")
      (node (ref "J7") (pin "1") (pinfunction "1_1") (pintype "passive"))
      (node (ref "J8") (pin "1") (pinfunction "1_1") (pintype "passive"))
    )
    (net (code "10") (name "Net-(J10-Pad1)") (class "Default")
      (node (ref "J10") (pin "1") (pinfunction "1_1") (pintype "passive"))
      (node (ref "J9") (pin "1") (pinfunction "1_1") (pintype "passive"))
    )
    (net (code "11") (name "Net-(J11-Pad1)") (class "Default")
      (node (ref "J11") (pin "1") (pinfunction "1_1") (pintype "passive"))
      (node (ref "J12") (pin "1") (pinfunction "1_1") (pintype "passive"))
    )
    (net (code "12") (name "Net-(J13-Pad1)") (class "Default")
      (node (ref "J13") (pin "1") (pinfunction "1_1") (pintype "passive"))
      (node (ref "J14") (pin "1") (pinfunction "1_1") (pintype "passive"))
    )
    (net (code "13") (name "Net-(J15-Pad1)") (class "Default")
      (node (ref "J15") (pin "1") (pinfunction "1_1") (pintype "passive"))
      (node (ref "J16") (pin "1") (pinfunction "1_1") (pintype "passive"))
    )
    (net (code "14") (name "Net-(J17-Pad1)") (class "Default")
      (node (ref "J17") (pin "1") (pinfunction "1_1") (pintype "passive"))
      (node (ref "J18") (pin "1") (pinfunction "1_1") (pintype "passive"))
    )
    (net (code "15") (name "Net-(J25-Pad1)") (class "Default")
      (node (ref "J25") (pin "1") (pinfunction "1_1") (pintype "passive"))
      (node (ref "J26") (pin "1") (pinfunction "1_1") (pintype "passive"))
      (node (ref "L3") (pin "1") (pinfunction "1_1") (pintype "passive"))
    )
    (net (code "16") (name "Net-(J29-Pad1)") (class "Default")
      (node (ref "J29") (pin "1") (pinfunction "1_1") (pintype "passive"))
      (node (ref "J30") (pin "1") (pinfunction "1_1") (pintype "passive"))
      (node (ref "L1") (pin "1") (pinfunction "1_1") (pintype "passive"))
    )
    (net (code "17") (name "unconnected-(0-Pad0)") (class "Default")
      (node (ref "0") (pin "0") (pinfunction "0_0") (pintype "passive"))
    )
    (net (code "18") (name "unconnected-(0-Pad0)_1") (class "Default")
      (node (ref "0") (pin "0") (pinfunction "0_0") (pintype "passive"))
    )
    (net (code "19") (name "unconnected-(0-Pad0)_2") (class "Default")
      (node (ref "0") (pin "0") (pinfunction "0_0") (pintype "passive"))
    )
    (net (code "20") (name "unconnected-(L1-Pad2)") (class "Default")
      (node (ref "L1") (pin "2") (pinfunction "2_2") (pintype "passive"))
    )
    (net (code "21") (name "unconnected-(L2-Pad2)") (class "Default")
      (node (ref "L2") (pin "2") (pinfunction "2_2") (pintype "passive"))
    )
    (net (code "22") (name "unconnected-(L3-Pad2)") (class "Default")
      (node (ref "L3") (pin "2") (pinfunction "2_2") (pintype "passive"))
    )
  )
)
